# FIDO2AUTH_00212.net
KiCad netlist of a schematic drawn in EAGLE
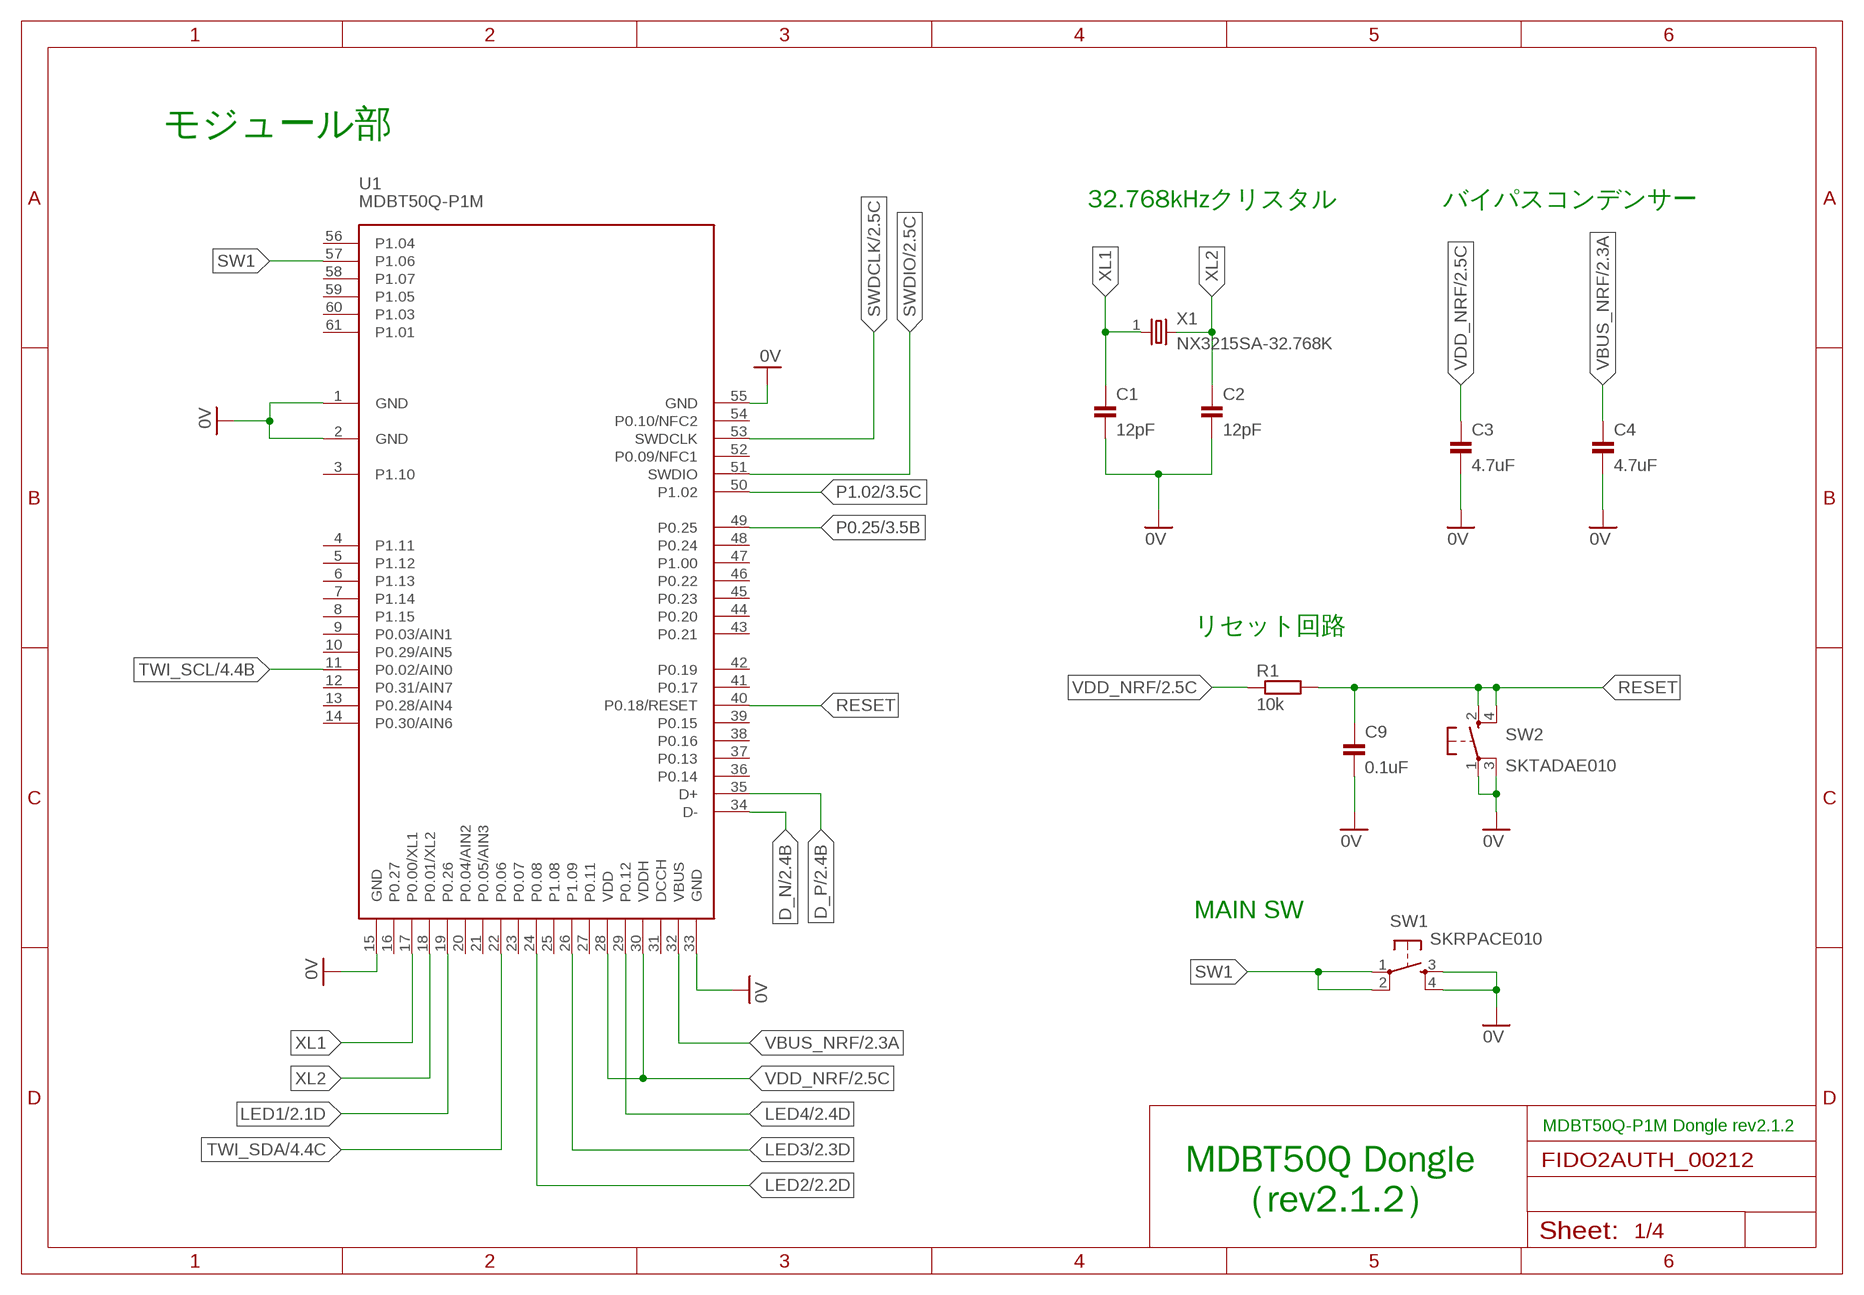
[diagram p0: schematic, sheet 1]
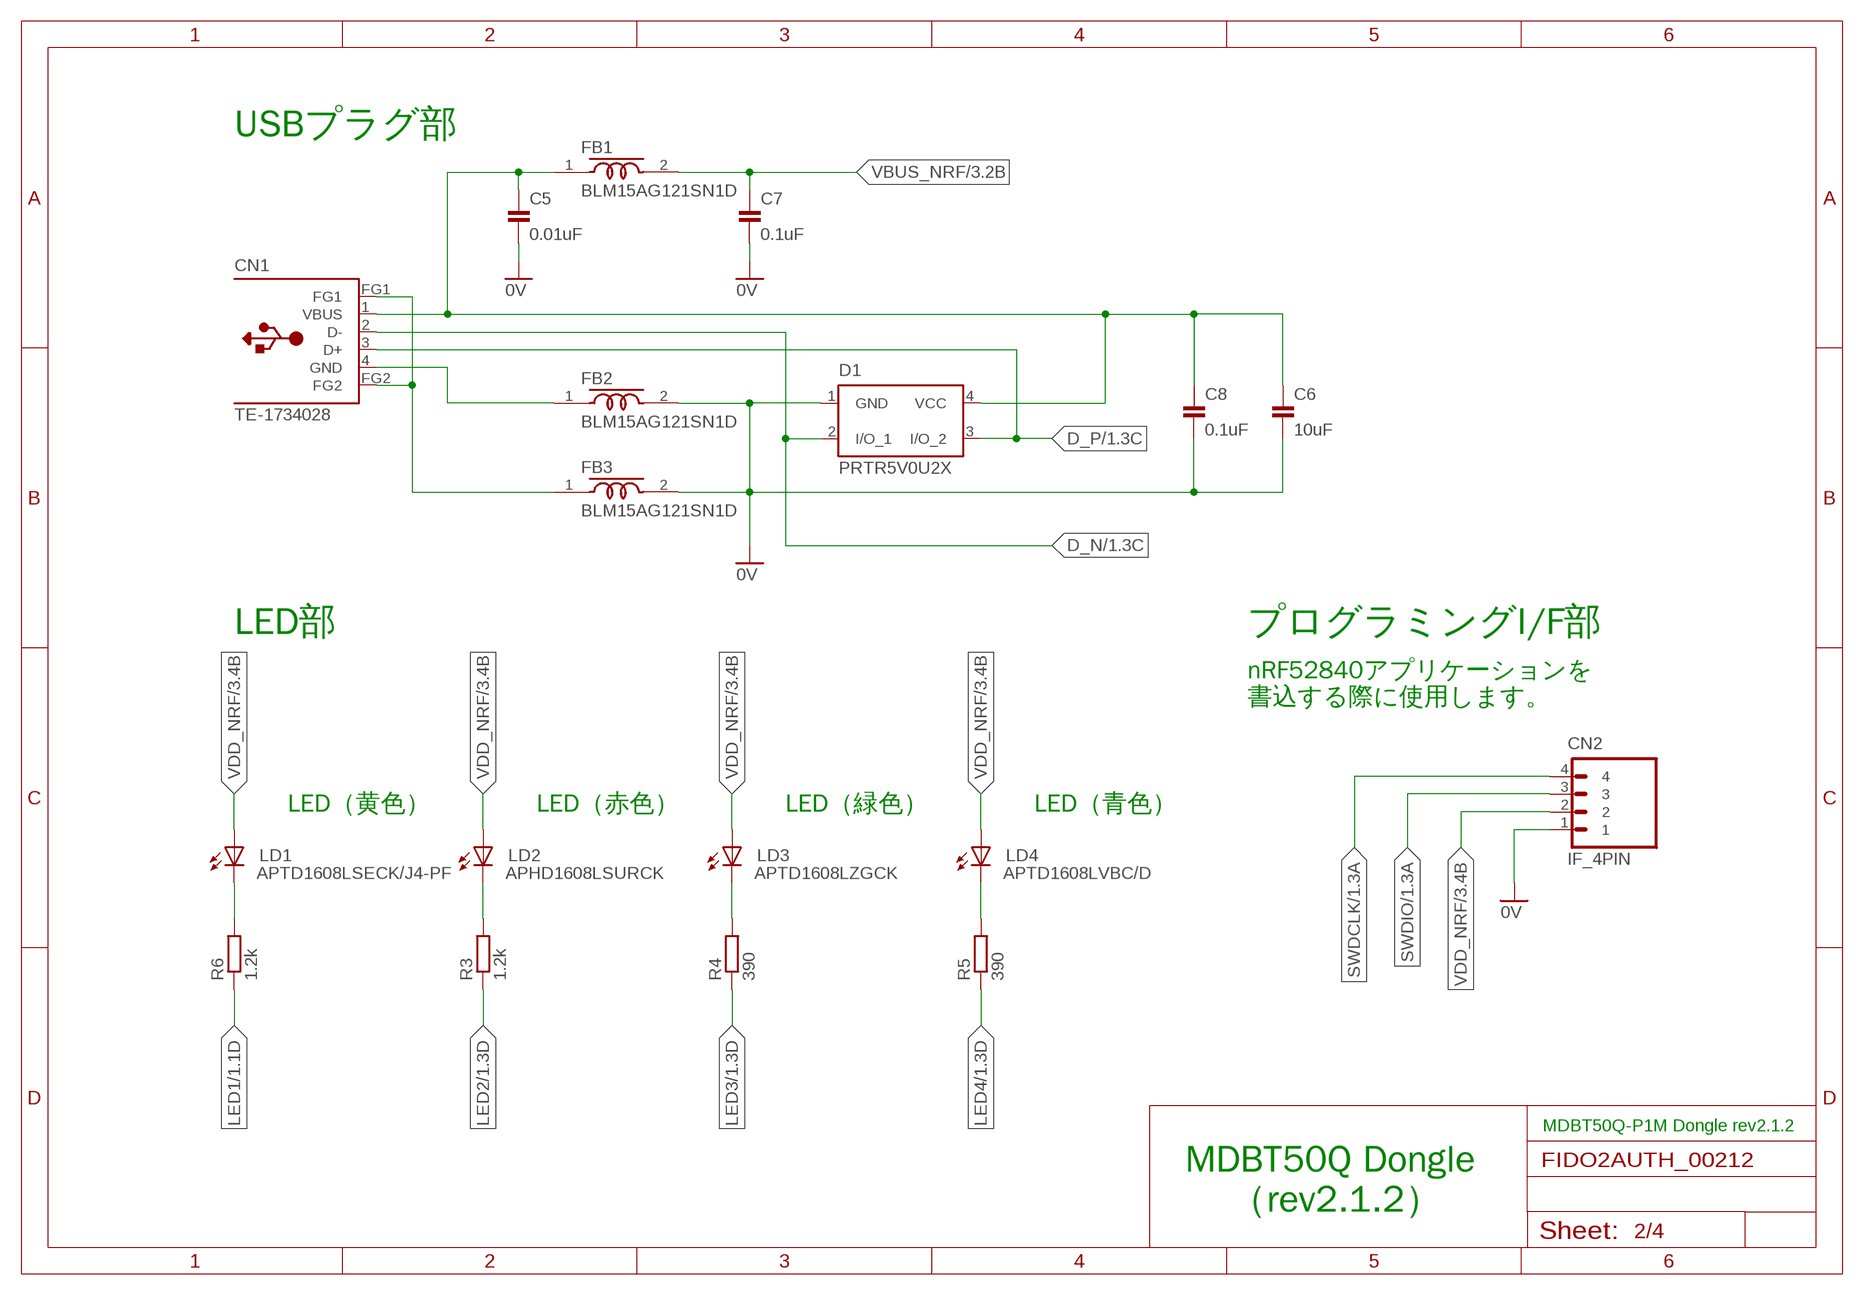
[diagram p1: schematic, sheet 2]
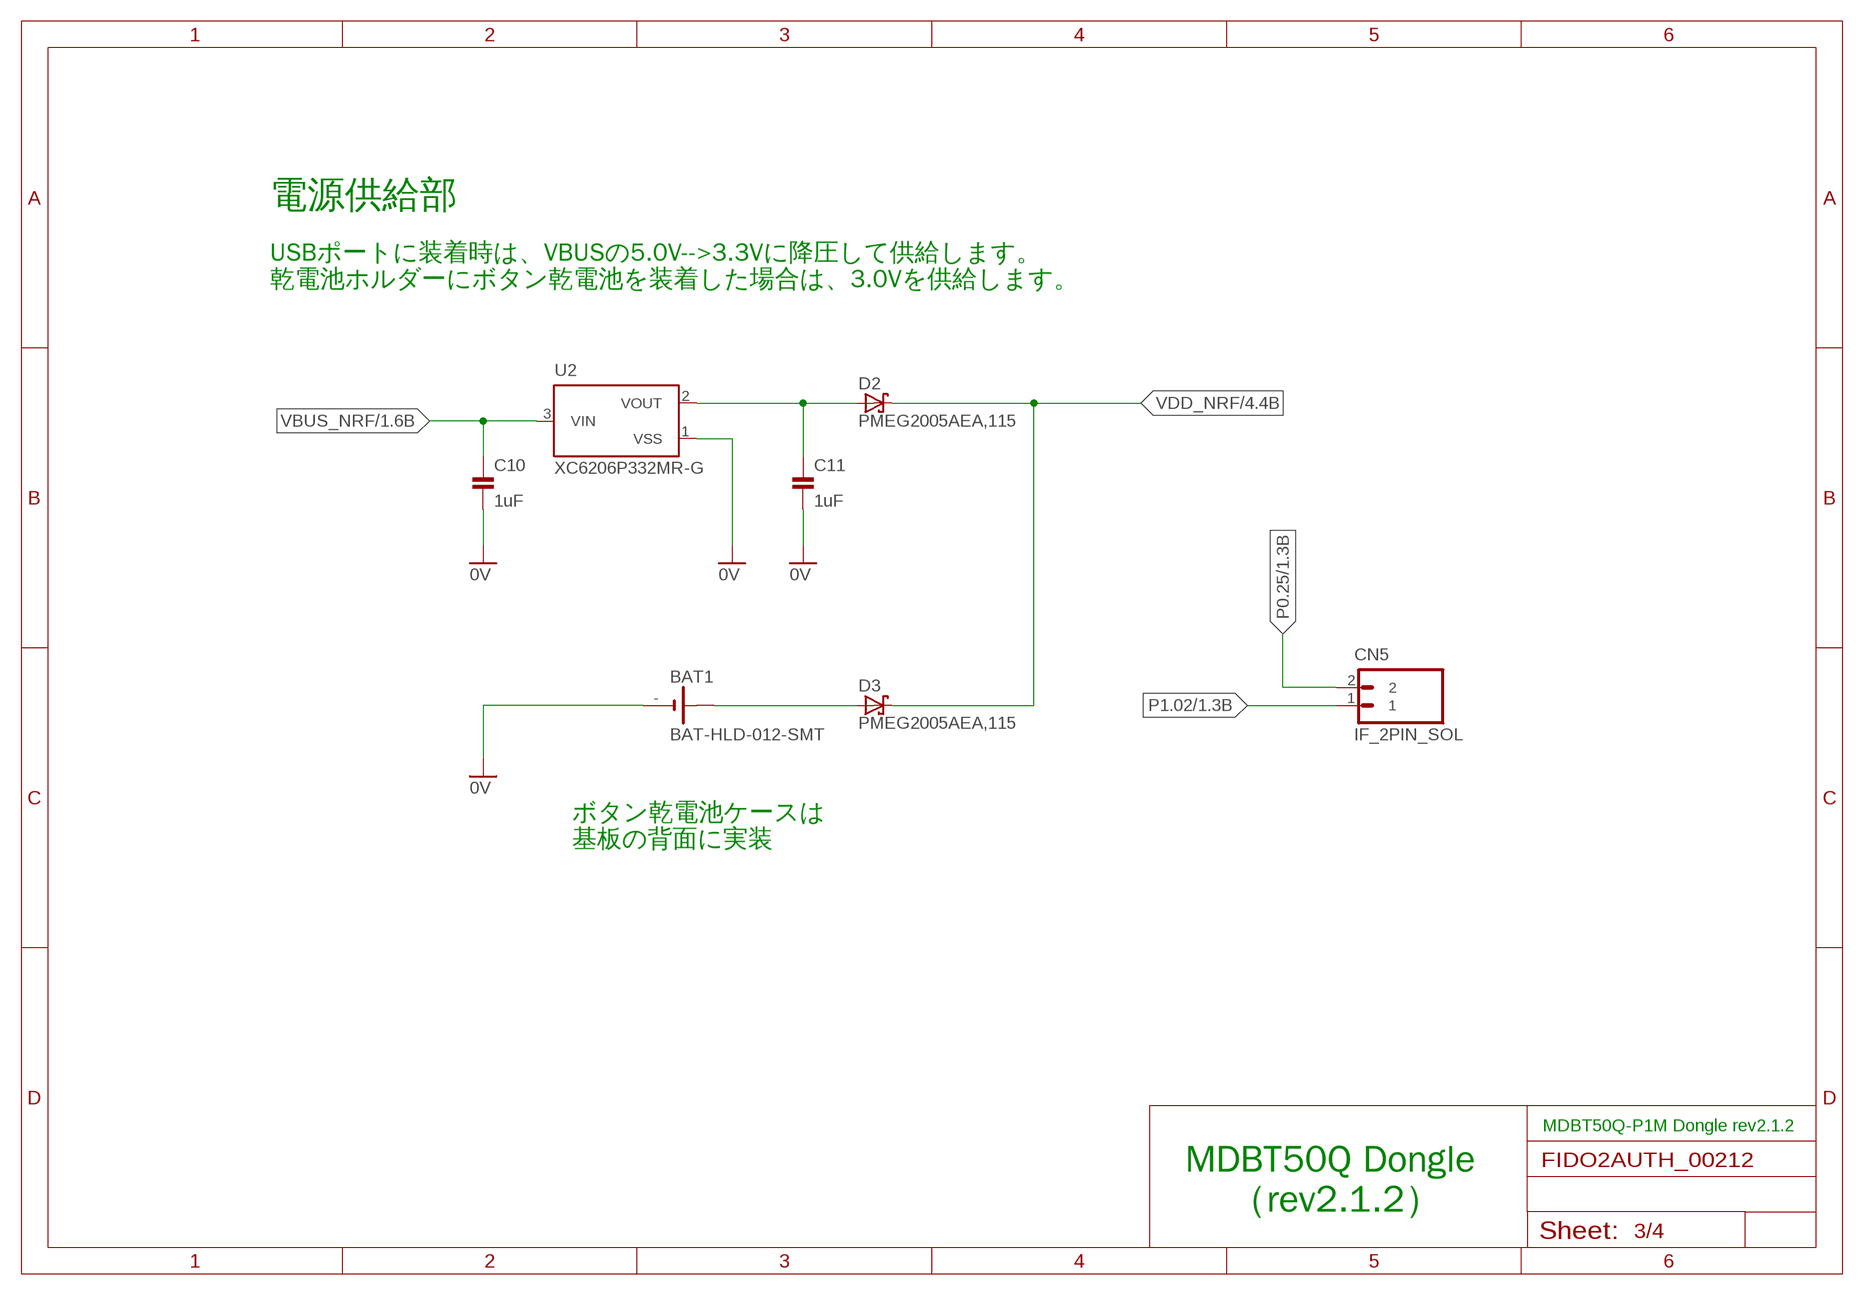
[diagram p2: schematic, sheet 3]
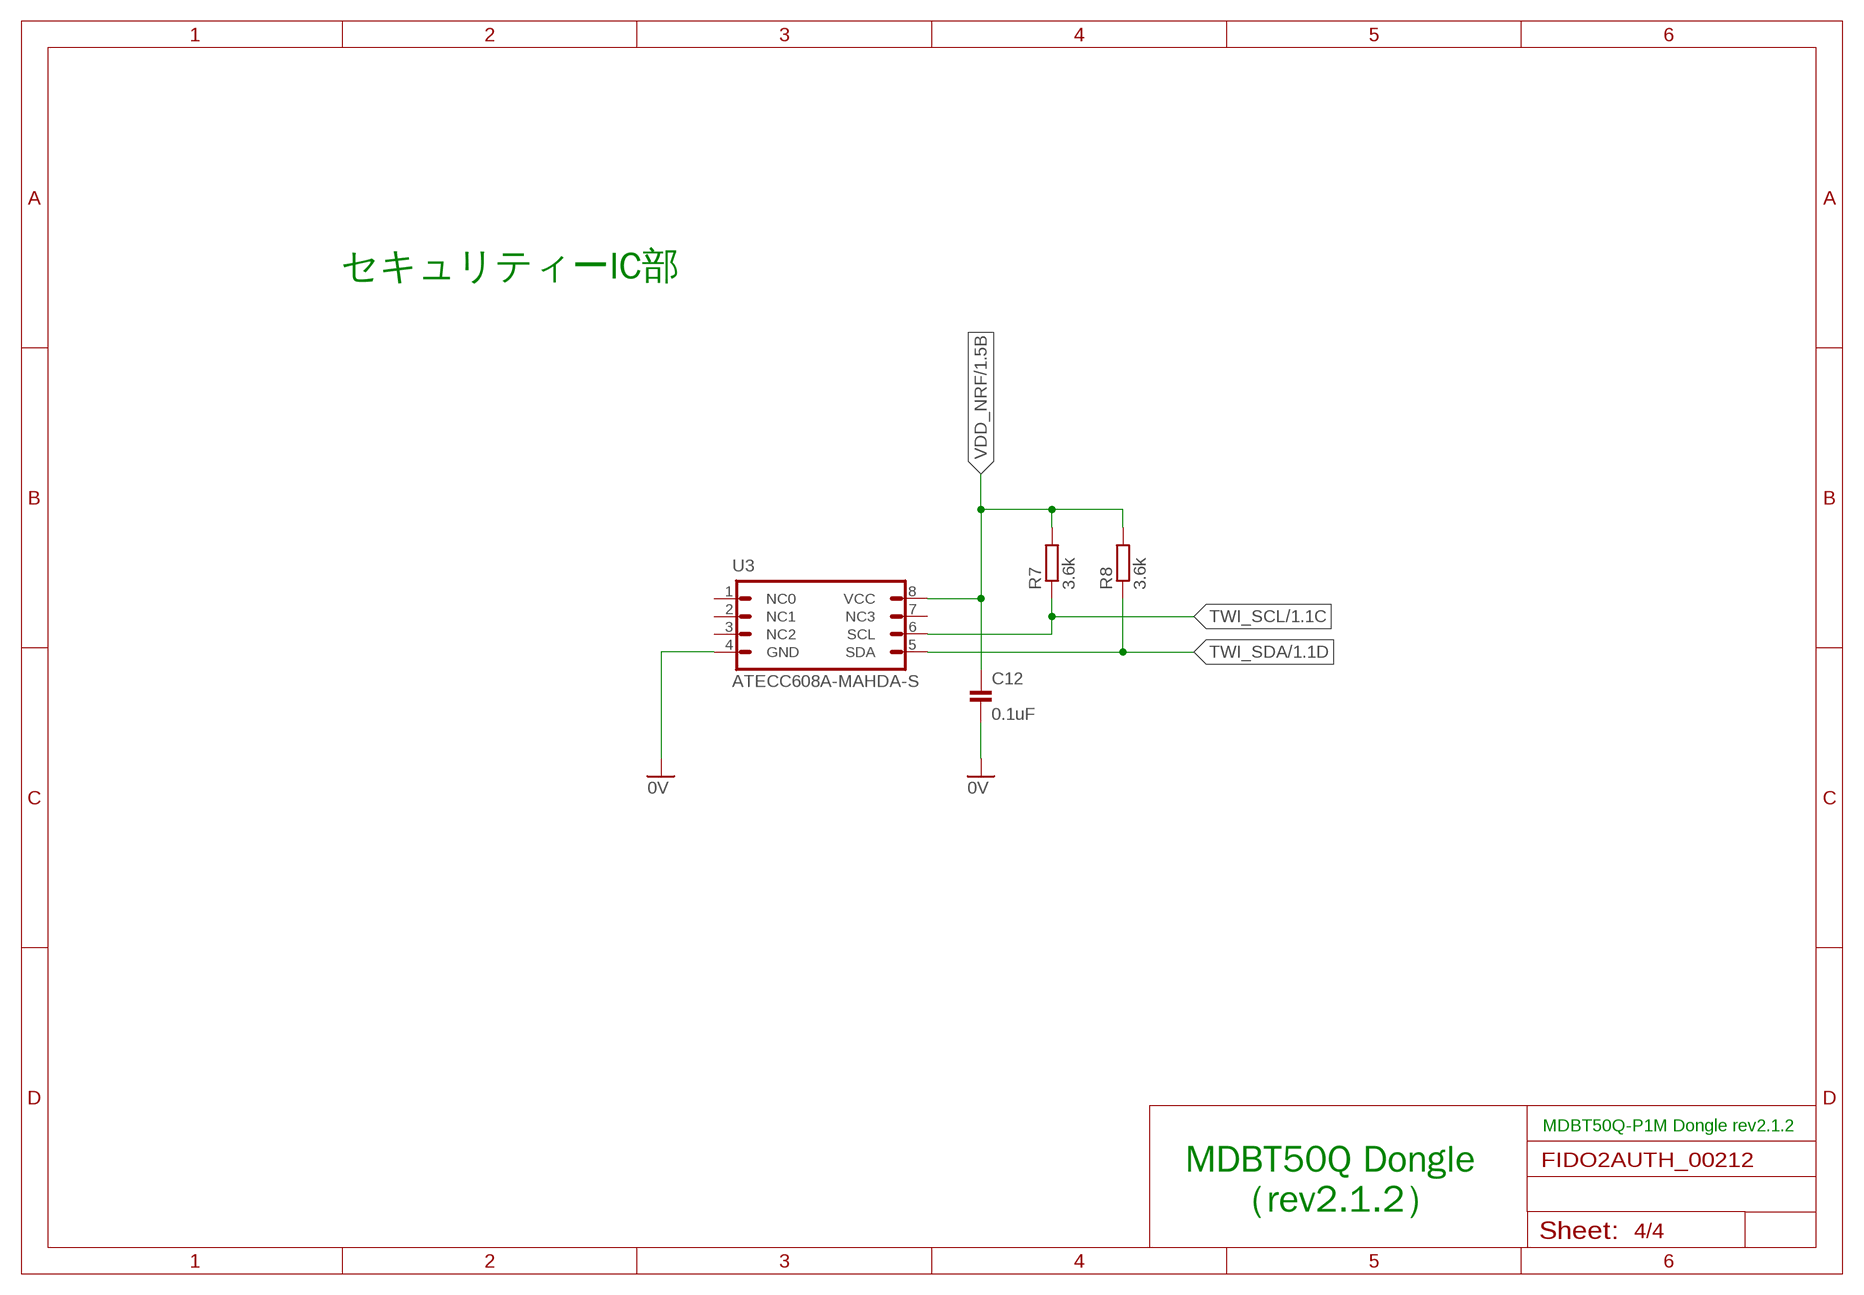
[diagram p3: schematic, sheet 4]

(export (version "E")
  (design (tool "Eeschema 10.0.6"))
  (components
    (comp (ref "C5")
      (value "0.01uF")
      (footprint "eagle-import:C0402K")
      (libsource (lib "eagle-import") (part "CAP_0402K"))
    )
    (comp (ref "C6")
      (value "10uF")
      (footprint "eagle-import:C0603K")
      (libsource (lib "eagle-import") (part "CAP_0603"))
    )
    (comp (ref "C7")
      (value "0.1uF")
      (footprint "eagle-import:C0402K")
      (libsource (lib "eagle-import") (part "CAP_0402K"))
    )
    (comp (ref "C8")
      (value "0.1uF")
      (footprint "eagle-import:C0402K")
      (libsource (lib "eagle-import") (part "CAP_0402K"))
    )
    (comp (ref "CN1")
      (value "TE-1734028")
      (footprint "eagle-import:TE-1734028")
      (libsource (lib "eagle-import") (part "TE-1734028"))
    )
    (comp (ref "CN2")
      (value "IF_4PIN")
      (footprint "eagle-import:HEADER_4PIN")
      (libsource (lib "eagle-import") (part "IF_4PIN"))
    )
    (comp (ref "D1")
      (value "PRTR5V0U2X")
      (footprint "eagle-import:SOT143B")
      (libsource (lib "eagle-import") (part "PRTR5V0U2X"))
    )
    (comp (ref "FB1")
      (value "BLM15AG121SN1D")
      (footprint "eagle-import:C0402K")
      (libsource (lib "eagle-import") (part "BLM15AG121SN1D"))
    )
    (comp (ref "FB2")
      (value "BLM15AG121SN1D")
      (footprint "eagle-import:C0402K")
      (libsource (lib "eagle-import") (part "BLM15AG121SN1D"))
    )
    (comp (ref "FB3")
      (value "BLM15AG121SN1D")
      (footprint "eagle-import:C0402K")
      (libsource (lib "eagle-import") (part "BLM15AG121SN1D"))
    )
    (comp (ref "LD1")
      (value "APTD1608LSECK/J4-PF")
      (footprint "eagle-import:APTD1608")
      (libsource (lib "eagle-import") (part "APTD1608LSECK/J4-PF"))
    )
    (comp (ref "LD2")
      (value "APHD1608LSURCK")
      (footprint "eagle-import:APTD1608")
      (libsource (lib "eagle-import") (part "APHD1608LSURCK"))
    )
    (comp (ref "LD3")
      (value "APTD1608LZGCK")
      (footprint "eagle-import:APTD1608")
      (libsource (lib "eagle-import") (part "APTD1608LZGCK"))
    )
    (comp (ref "LD4")
      (value "APTD1608LVBC/D")
      (footprint "eagle-import:APTD1608")
      (libsource (lib "eagle-import") (part "APTD1608LVBC/D"))
    )
    (comp (ref "R3")
      (value "1.2k")
      (footprint "eagle-import:R0402")
      (libsource (lib "eagle-import") (part "RESISTOR_0402"))
    )
    (comp (ref "R4")
      (value "390")
      (footprint "eagle-import:R0402")
      (libsource (lib "eagle-import") (part "RESISTOR_0402"))
    )
    (comp (ref "R5")
      (value "390")
      (footprint "eagle-import:R0402")
      (libsource (lib "eagle-import") (part "RESISTOR_0402"))
    )
    (comp (ref "R6")
      (value "1.2k")
      (footprint "eagle-import:R0402")
      (libsource (lib "eagle-import") (part "RESISTOR_0402"))
    )
    (comp (ref "C12")
      (value "0.1uF")
      (footprint "eagle-import:C0402K")
      (libsource (lib "eagle-import") (part "CAP_0402K"))
    )
    (comp (ref "R7")
      (value "3.6k")
      (footprint "eagle-import:R0402")
      (libsource (lib "eagle-import") (part "RESISTOR_0402"))
    )
    (comp (ref "R8")
      (value "3.6k")
      (footprint "eagle-import:R0402")
      (libsource (lib "eagle-import") (part "RESISTOR_0402"))
    )
    (comp (ref "U3")
      (value "ATECC608A-MAHDA-S")
      (footprint "eagle-import:DFN-2X3")
      (libsource (lib "eagle-import") (part "ATECC608A-MAHDA-S"))
    )
    (comp (ref "C1")
      (value "12pF")
      (footprint "eagle-import:C0603K")
      (libsource (lib "eagle-import") (part "CAP_0603"))
    )
    (comp (ref "C2")
      (value "12pF")
      (footprint "eagle-import:C0603K")
      (libsource (lib "eagle-import") (part "CAP_0603"))
    )
    (comp (ref "C3")
      (value "4.7uF")
      (footprint "eagle-import:C0603K")
      (libsource (lib "eagle-import") (part "CAP_0603"))
    )
    (comp (ref "C4")
      (value "4.7uF")
      (footprint "eagle-import:C0603K")
      (libsource (lib "eagle-import") (part "CAP_0603"))
    )
    (comp (ref "C9")
      (value "0.1uF")
      (footprint "eagle-import:C0402K")
      (libsource (lib "eagle-import") (part "CAP_0402K"))
    )
    (comp (ref "R1")
      (value "10k")
      (footprint "eagle-import:R0402")
      (libsource (lib "eagle-import") (part "RESISTOR_0402"))
    )
    (comp (ref "SW1")
      (value "SKRPACE010")
      (footprint "eagle-import:SKRPACE010")
      (libsource (lib "eagle-import") (part "SKRPACE010"))
    )
    (comp (ref "SW2")
      (value "SKTADAE010")
      (footprint "eagle-import:SKTADAE010")
      (libsource (lib "eagle-import") (part "SKTADAE010"))
    )
    (comp (ref "U1")
      (value "MDBT50Q-P1M")
      (footprint "eagle-import:MDBT50Q-P1M")
      (libsource (lib "eagle-import") (part "MDBT50Q-P1M"))
    )
    (comp (ref "X1")
      (value "NX3215SA-32.768K")
      (footprint "eagle-import:NX3215")
      (libsource (lib "eagle-import") (part "NX3215SA-32.768K"))
    )
    (comp (ref "BAT1")
      (value "BAT-HLD-012-SMT")
      (footprint "eagle-import:BAT-HLD-012-SMT")
      (libsource (lib "eagle-import") (part "BAT-HLD-012-SMT"))
    )
    (comp (ref "C10")
      (value "1uF")
      (footprint "eagle-import:C0603K")
      (libsource (lib "eagle-import") (part "CAP_0603"))
    )
    (comp (ref "C11")
      (value "1uF")
      (footprint "eagle-import:C0603K")
      (libsource (lib "eagle-import") (part "CAP_0603"))
    )
    (comp (ref "CN5")
      (value "IF_2PIN_SOL")
      (footprint "eagle-import:SOLPAD_2PIN")
      (libsource (lib "eagle-import") (part "IF_2PIN_SOL"))
    )
    (comp (ref "D2")
      (value "PMEG2005AEA,115")
      (footprint "eagle-import:SOD323-W")
      (libsource (lib "eagle-import") (part "PMEG2005AEA,115"))
    )
    (comp (ref "D3")
      (value "PMEG2005AEA,115")
      (footprint "eagle-import:SOD323-W")
      (libsource (lib "eagle-import") (part "PMEG2005AEA,115"))
    )
    (comp (ref "U2")
      (value "XC6206P332MR-G")
      (footprint "eagle-import:SOT23")
      (libsource (lib "eagle-import") (part "XC6206P332MR-G"))
    )
  )
  (nets
    (net (code "1") (name "0V") (class "Default")
      (node (ref "BAT1") (pin "-") (pinfunction "-_-") (pintype "passive"))
      (node (ref "C1") (pin "2") (pinfunction "2_2") (pintype "passive"))
      (node (ref "C10") (pin "2") (pinfunction "2_2") (pintype "passive"))
      (node (ref "C11") (pin "2") (pinfunction "2_2") (pintype "passive"))
      (node (ref "C12") (pin "2") (pinfunction "2_2") (pintype "passive"))
      (node (ref "C2") (pin "2") (pinfunction "2_2") (pintype "passive"))
      (node (ref "C3") (pin "2") (pinfunction "2_2") (pintype "passive"))
      (node (ref "C4") (pin "2") (pinfunction "2_2") (pintype "passive"))
      (node (ref "C5") (pin "2") (pinfunction "2_2") (pintype "passive"))
      (node (ref "C6") (pin "2") (pinfunction "2_2") (pintype "passive"))
      (node (ref "C7") (pin "2") (pinfunction "2_2") (pintype "passive"))
      (node (ref "C8") (pin "2") (pinfunction "2_2") (pintype "passive"))
      (node (ref "C9") (pin "2") (pinfunction "2_2") (pintype "passive"))
      (node (ref "CN2") (pin "1") (pinfunction "1_1") (pintype "passive"))
      (node (ref "D1") (pin "1") (pinfunction "GND_1") (pintype "passive"))
      (node (ref "FB2") (pin "2") (pinfunction "2_2") (pintype "passive"))
      (node (ref "FB3") (pin "2") (pinfunction "2_2") (pintype "passive"))
      (node (ref "SW1") (pin "3") (pinfunction "S_3") (pintype "passive"))
      (node (ref "SW1") (pin "4") (pinfunction "S1_4") (pintype "passive"))
      (node (ref "SW2") (pin "1") (pinfunction "P_1") (pintype "passive"))
      (node (ref "SW2") (pin "3") (pinfunction "P1_3") (pintype "passive"))
      (node (ref "U1") (pin "1") (pinfunction "GND_1") (pintype "bidirectional"))
      (node (ref "U1") (pin "15") (pinfunction "GND_15") (pintype "bidirectional"))
      (node (ref "U1") (pin "2") (pinfunction "GND_2") (pintype "bidirectional"))
      (node (ref "U1") (pin "33") (pinfunction "GND_33") (pintype "bidirectional"))
      (node (ref "U1") (pin "55") (pinfunction "GND_55") (pintype "bidirectional"))
      (node (ref "U2") (pin "1") (pinfunction "VSS_1") (pintype "passive"))
      (node (ref "U3") (pin "4") (pinfunction "GND_4") (pintype "passive"))
    )
    (net (code "2") (name "D_N") (class "Default")
      (node (ref "CN1") (pin "2") (pinfunction "D-_2") (pintype "bidirectional"))
      (node (ref "D1") (pin "2") (pinfunction "I/O_1_2") (pintype "bidirectional"))
      (node (ref "U1") (pin "34") (pinfunction "D-_34") (pintype "bidirectional"))
    )
    (net (code "3") (name "D_P") (class "Default")
      (node (ref "CN1") (pin "3") (pinfunction "D+_3") (pintype "bidirectional"))
      (node (ref "D1") (pin "3") (pinfunction "I/O_2_3") (pintype "bidirectional"))
      (node (ref "U1") (pin "35") (pinfunction "D+_35") (pintype "bidirectional"))
    )
    (net (code "4") (name "LED1") (class "Default")
      (node (ref "R6") (pin "1") (pinfunction "1_1") (pintype "passive"))
      (node (ref "U1") (pin "19") (pinfunction "P0.26_19") (pintype "bidirectional"))
    )
    (net (code "5") (name "LED2") (class "Default")
      (node (ref "R3") (pin "1") (pinfunction "1_1") (pintype "passive"))
      (node (ref "U1") (pin "24") (pinfunction "P0.08_24") (pintype "bidirectional"))
    )
    (net (code "6") (name "LED3") (class "Default")
      (node (ref "R4") (pin "1") (pinfunction "1_1") (pintype "passive"))
      (node (ref "U1") (pin "26") (pinfunction "P1.09_26") (pintype "bidirectional"))
    )
    (net (code "7") (name "LED4") (class "Default")
      (node (ref "R5") (pin "1") (pinfunction "1_1") (pintype "passive"))
      (node (ref "U1") (pin "29") (pinfunction "P0.12_29") (pintype "bidirectional"))
    )
    (net (code "8") (name "Net-(BAT1-+)") (class "Default")
      (node (ref "BAT1") (pin "+@1") (pinfunction "+_+@1") (pintype "passive"))
      (node (ref "D3") (pin "A") (pinfunction "A_A") (pintype "passive"))
    )
    (net (code "9") (name "Net-(CN1-GND)") (class "Default")
      (node (ref "CN1") (pin "4") (pinfunction "GND_4") (pintype "passive"))
      (node (ref "FB2") (pin "1") (pinfunction "1_1") (pintype "passive"))
    )
    (net (code "10") (name "Net-(CN1-PadFG1)") (class "Default")
      (node (ref "CN1") (pin "FG1") (pinfunction "FG1_FG1") (pintype "passive"))
      (node (ref "CN1") (pin "FG2") (pinfunction "FG2_FG2") (pintype "passive"))
      (node (ref "FB3") (pin "1") (pinfunction "1_1") (pintype "passive"))
    )
    (net (code "11") (name "Net-(CN1-VBUS)") (class "Default")
      (node (ref "C5") (pin "1") (pinfunction "1_1") (pintype "passive"))
      (node (ref "C6") (pin "1") (pinfunction "1_1") (pintype "passive"))
      (node (ref "C8") (pin "1") (pinfunction "1_1") (pintype "passive"))
      (node (ref "CN1") (pin "1") (pinfunction "VBUS_1") (pintype "passive"))
      (node (ref "D1") (pin "4") (pinfunction "VCC_4") (pintype "passive"))
      (node (ref "FB1") (pin "1") (pinfunction "1_1") (pintype "passive"))
    )
    (net (code "12") (name "Net-(LD1-PadC)") (class "Default")
      (node (ref "LD1") (pin "C") (pinfunction "C_C") (pintype "passive"))
      (node (ref "R6") (pin "2") (pinfunction "2_2") (pintype "passive"))
    )
    (net (code "13") (name "Net-(LD2-PadC)") (class "Default")
      (node (ref "LD2") (pin "C") (pinfunction "C_C") (pintype "passive"))
      (node (ref "R3") (pin "2") (pinfunction "2_2") (pintype "passive"))
    )
    (net (code "14") (name "Net-(LD3-PadC)") (class "Default")
      (node (ref "LD3") (pin "C") (pinfunction "C_C") (pintype "passive"))
      (node (ref "R4") (pin "2") (pinfunction "2_2") (pintype "passive"))
    )
    (net (code "15") (name "Net-(LD4-PadC)") (class "Default")
      (node (ref "LD4") (pin "C") (pinfunction "C_C") (pintype "passive"))
      (node (ref "R5") (pin "2") (pinfunction "2_2") (pintype "passive"))
    )
    (net (code "16") (name "Net-(U2-VOUT)") (class "Default")
      (node (ref "C11") (pin "1") (pinfunction "1_1") (pintype "passive"))
      (node (ref "D2") (pin "A") (pinfunction "A_A") (pintype "passive"))
      (node (ref "U2") (pin "2") (pinfunction "VOUT_2") (pintype "passive"))
    )
    (net (code "17") (name "P0.25") (class "Default")
      (node (ref "CN5") (pin "2") (pinfunction "2_2") (pintype "passive"))
      (node (ref "U1") (pin "49") (pinfunction "P0.25_49") (pintype "bidirectional"))
    )
    (net (code "18") (name "P1.02") (class "Default")
      (node (ref "CN5") (pin "1") (pinfunction "1_1") (pintype "passive"))
      (node (ref "U1") (pin "50") (pinfunction "P1.02_50") (pintype "bidirectional"))
    )
    (net (code "19") (name "RESET") (class "Default")
      (node (ref "C9") (pin "1") (pinfunction "1_1") (pintype "passive"))
      (node (ref "R1") (pin "2") (pinfunction "2_2") (pintype "passive"))
      (node (ref "SW2") (pin "2") (pinfunction "S_2") (pintype "passive"))
      (node (ref "SW2") (pin "4") (pinfunction "S1_4") (pintype "passive"))
      (node (ref "U1") (pin "40") (pinfunction "P0.18/RESET_40") (pintype "bidirectional"))
    )
    (net (code "20") (name "SW1") (class "Default")
      (node (ref "SW1") (pin "1") (pinfunction "P_1") (pintype "passive"))
      (node (ref "SW1") (pin "2") (pinfunction "P1_2") (pintype "passive"))
      (node (ref "U1") (pin "57") (pinfunction "P1.06_57") (pintype "bidirectional"))
    )
    (net (code "21") (name "SWDCLK") (class "Default")
      (node (ref "CN2") (pin "4") (pinfunction "4_4") (pintype "passive"))
      (node (ref "U1") (pin "53") (pinfunction "SWDCLK_53") (pintype "bidirectional"))
    )
    (net (code "22") (name "SWDIO") (class "Default")
      (node (ref "CN2") (pin "3") (pinfunction "3_3") (pintype "passive"))
      (node (ref "U1") (pin "51") (pinfunction "SWDIO_51") (pintype "bidirectional"))
    )
    (net (code "23") (name "TWI_SCL") (class "Default")
      (node (ref "R7") (pin "1") (pinfunction "1_1") (pintype "passive"))
      (node (ref "U1") (pin "11") (pinfunction "P0.02/AIN0_11") (pintype "bidirectional"))
      (node (ref "U3") (pin "6") (pinfunction "SCL_6") (pintype "bidirectional"))
    )
    (net (code "24") (name "TWI_SDA") (class "Default")
      (node (ref "R8") (pin "1") (pinfunction "1_1") (pintype "passive"))
      (node (ref "U1") (pin "22") (pinfunction "P0.06_22") (pintype "bidirectional"))
      (node (ref "U3") (pin "5") (pinfunction "SDA_5") (pintype "bidirectional"))
    )
    (net (code "25") (name "VBUS_NRF") (class "Default")
      (node (ref "C10") (pin "1") (pinfunction "1_1") (pintype "passive"))
      (node (ref "C4") (pin "1") (pinfunction "1_1") (pintype "passive"))
      (node (ref "C7") (pin "1") (pinfunction "1_1") (pintype "passive"))
      (node (ref "FB1") (pin "2") (pinfunction "2_2") (pintype "passive"))
      (node (ref "U1") (pin "32") (pinfunction "VBUS_32") (pintype "bidirectional"))
      (node (ref "U2") (pin "3") (pinfunction "VIN_3") (pintype "passive"))
    )
    (net (code "26") (name "VDD_NRF") (class "Default")
      (node (ref "C12") (pin "1") (pinfunction "1_1") (pintype "passive"))
      (node (ref "C3") (pin "1") (pinfunction "1_1") (pintype "passive"))
      (node (ref "CN2") (pin "2") (pinfunction "2_2") (pintype "passive"))
      (node (ref "D2") (pin "C") (pinfunction "C_C") (pintype "passive"))
      (node (ref "D3") (pin "C") (pinfunction "C_C") (pintype "passive"))
      (node (ref "LD1") (pin "A") (pinfunction "A_A") (pintype "passive"))
      (node (ref "LD2") (pin "A") (pinfunction "A_A") (pintype "passive"))
      (node (ref "LD3") (pin "A") (pinfunction "A_A") (pintype "passive"))
      (node (ref "LD4") (pin "A") (pinfunction "A_A") (pintype "passive"))
      (node (ref "R1") (pin "1") (pinfunction "1_1") (pintype "passive"))
      (node (ref "R7") (pin "2") (pinfunction "2_2") (pintype "passive"))
      (node (ref "R8") (pin "2") (pinfunction "2_2") (pintype "passive"))
      (node (ref "U1") (pin "28") (pinfunction "VDD_28") (pintype "bidirectional"))
      (node (ref "U1") (pin "30") (pinfunction "VDDH_30") (pintype "bidirectional"))
      (node (ref "U3") (pin "8") (pinfunction "VCC_8") (pintype "passive"))
    )
    (net (code "27") (name "XL1") (class "Default")
      (node (ref "C1") (pin "1") (pinfunction "1_1") (pintype "passive"))
      (node (ref "U1") (pin "17") (pinfunction "P0.00/XL1_17") (pintype "bidirectional"))
      (node (ref "X1") (pin "1") (pinfunction "1_1") (pintype "passive"))
    )
    (net (code "28") (name "XL2") (class "Default")
      (node (ref "C2") (pin "1") (pinfunction "1_1") (pintype "passive"))
      (node (ref "U1") (pin "18") (pinfunction "P0.01/XL2_18") (pintype "bidirectional"))
      (node (ref "X1") (pin "2") (pinfunction "2_2") (pintype "passive"))
    )
    (net (code "29") (name "unconnected-(U1-DCCH-Pad31)") (class "Default")
      (node (ref "U1") (pin "31") (pinfunction "DCCH_31") (pintype "bidirectional"))
    )
    (net (code "30") (name "unconnected-(U1-P0.03{slash}AIN1-Pad9)") (class "Default")
      (node (ref "U1") (pin "9") (pinfunction "P0.03/AIN1_9") (pintype "bidirectional"))
    )
    (net (code "31") (name "unconnected-(U1-P0.04{slash}AIN2-Pad20)") (class "Default")
      (node (ref "U1") (pin "20") (pinfunction "P0.04/AIN2_20") (pintype "bidirectional"))
    )
    (net (code "32") (name "unconnected-(U1-P0.05{slash}AIN3-Pad21)") (class "Default")
      (node (ref "U1") (pin "21") (pinfunction "P0.05/AIN3_21") (pintype "bidirectional"))
    )
    (net (code "33") (name "unconnected-(U1-P0.07-Pad23)") (class "Default")
      (node (ref "U1") (pin "23") (pinfunction "P0.07_23") (pintype "bidirectional"))
    )
    (net (code "34") (name "unconnected-(U1-P0.09{slash}NFC1-Pad52)") (class "Default")
      (node (ref "U1") (pin "52") (pinfunction "P0.09/NFC1_52") (pintype "bidirectional"))
    )
    (net (code "35") (name "unconnected-(U1-P0.10{slash}NFC2-Pad54)") (class "Default")
      (node (ref "U1") (pin "54") (pinfunction "P0.10/NFC2_54") (pintype "bidirectional"))
    )
    (net (code "36") (name "unconnected-(U1-P0.11-Pad27)") (class "Default")
      (node (ref "U1") (pin "27") (pinfunction "P0.11_27") (pintype "bidirectional"))
    )
    (net (code "37") (name "unconnected-(U1-P0.13-Pad37)") (class "Default")
      (node (ref "U1") (pin "37") (pinfunction "P0.13_37") (pintype "bidirectional"))
    )
    (net (code "38") (name "unconnected-(U1-P0.14-Pad36)") (class "Default")
      (node (ref "U1") (pin "36") (pinfunction "P0.14_36") (pintype "bidirectional"))
    )
    (net (code "39") (name "unconnected-(U1-P0.15-Pad39)") (class "Default")
      (node (ref "U1") (pin "39") (pinfunction "P0.15_39") (pintype "bidirectional"))
    )
    (net (code "40") (name "unconnected-(U1-P0.16-Pad38)") (class "Default")
      (node (ref "U1") (pin "38") (pinfunction "P0.16_38") (pintype "bidirectional"))
    )
    (net (code "41") (name "unconnected-(U1-P0.17-Pad41)") (class "Default")
      (node (ref "U1") (pin "41") (pinfunction "P0.17_41") (pintype "bidirectional"))
    )
    (net (code "42") (name "unconnected-(U1-P0.19-Pad42)") (class "Default")
      (node (ref "U1") (pin "42") (pinfunction "P0.19_42") (pintype "bidirectional"))
    )
    (net (code "43") (name "unconnected-(U1-P0.20-Pad44)") (class "Default")
      (node (ref "U1") (pin "44") (pinfunction "P0.20_44") (pintype "bidirectional"))
    )
    (net (code "44") (name "unconnected-(U1-P0.21-Pad43)") (class "Default")
      (node (ref "U1") (pin "43") (pinfunction "P0.21_43") (pintype "bidirectional"))
    )
    (net (code "45") (name "unconnected-(U1-P0.22-Pad46)") (class "Default")
      (node (ref "U1") (pin "46") (pinfunction "P0.22_46") (pintype "bidirectional"))
    )
    (net (code "46") (name "unconnected-(U1-P0.23-Pad45)") (class "Default")
      (node (ref "U1") (pin "45") (pinfunction "P0.23_45") (pintype "bidirectional"))
    )
    (net (code "47") (name "unconnected-(U1-P0.24-Pad48)") (class "Default")
      (node (ref "U1") (pin "48") (pinfunction "P0.24_48") (pintype "bidirectional"))
    )
    (net (code "48") (name "unconnected-(U1-P0.27-Pad16)") (class "Default")
      (node (ref "U1") (pin "16") (pinfunction "P0.27_16") (pintype "bidirectional"))
    )
    (net (code "49") (name "unconnected-(U1-P0.28{slash}AIN4-Pad13)") (class "Default")
      (node (ref "U1") (pin "13") (pinfunction "P0.28/AIN4_13") (pintype "bidirectional"))
    )
    (net (code "50") (name "unconnected-(U1-P0.29{slash}AIN5-Pad10)") (class "Default")
      (node (ref "U1") (pin "10") (pinfunction "P0.29/AIN5_10") (pintype "bidirectional"))
    )
    (net (code "51") (name "unconnected-(U1-P0.30{slash}AIN6-Pad14)") (class "Default")
      (node (ref "U1") (pin "14") (pinfunction "P0.30/AIN6_14") (pintype "bidirectional"))
    )
    (net (code "52") (name "unconnected-(U1-P0.31{slash}AIN7-Pad12)") (class "Default")
      (node (ref "U1") (pin "12") (pinfunction "P0.31/AIN7_12") (pintype "bidirectional"))
    )
    (net (code "53") (name "unconnected-(U1-P1.00-Pad47)") (class "Default")
      (node (ref "U1") (pin "47") (pinfunction "P1.00_47") (pintype "bidirectional"))
    )
    (net (code "54") (name "unconnected-(U1-P1.01-Pad61)") (class "Default")
      (node (ref "U1") (pin "61") (pinfunction "P1.01_61") (pintype "bidirectional"))
    )
    (net (code "55") (name "unconnected-(U1-P1.03-Pad60)") (class "Default")
      (node (ref "U1") (pin "60") (pinfunction "P1.03_60") (pintype "bidirectional"))
    )
    (net (code "56") (name "unconnected-(U1-P1.04-Pad56)") (class "Default")
      (node (ref "U1") (pin "56") (pinfunction "P1.04_56") (pintype "bidirectional"))
    )
    (net (code "57") (name "unconnected-(U1-P1.05-Pad59)") (class "Default")
      (node (ref "U1") (pin "59") (pinfunction "P1.05_59") (pintype "bidirectional"))
    )
    (net (code "58") (name "unconnected-(U1-P1.07-Pad58)") (class "Default")
      (node (ref "U1") (pin "58") (pinfunction "P1.07_58") (pintype "bidirectional"))
    )
    (net (code "59") (name "unconnected-(U1-P1.08-Pad25)") (class "Default")
      (node (ref "U1") (pin "25") (pinfunction "P1.08_25") (pintype "bidirectional"))
    )
    (net (code "60") (name "unconnected-(U1-P1.10-Pad3)") (class "Default")
      (node (ref "U1") (pin "3") (pinfunction "P1.10_3") (pintype "bidirectional"))
    )
    (net (code "61") (name "unconnected-(U1-P1.11-Pad4)") (class "Default")
      (node (ref "U1") (pin "4") (pinfunction "P1.11_4") (pintype "bidirectional"))
    )
    (net (code "62") (name "unconnected-(U1-P1.12-Pad5)") (class "Default")
      (node (ref "U1") (pin "5") (pinfunction "P1.12_5") (pintype "bidirectional"))
    )
    (net (code "63") (name "unconnected-(U1-P1.13-Pad6)") (class "Default")
      (node (ref "U1") (pin "6") (pinfunction "P1.13_6") (pintype "bidirectional"))
    )
    (net (code "64") (name "unconnected-(U1-P1.14-Pad7)") (class "Default")
      (node (ref "U1") (pin "7") (pinfunction "P1.14_7") (pintype "bidirectional"))
    )
    (net (code "65") (name "unconnected-(U1-P1.15-Pad8)") (class "Default")
      (node (ref "U1") (pin "8") (pinfunction "P1.15_8") (pintype "bidirectional"))
    )
    (net (code "66") (name "unconnected-(U3-NC0-Pad1)") (class "Default")
      (node (ref "U3") (pin "1") (pinfunction "NC0_1") (pintype "passive"))
    )
    (net (code "67") (name "unconnected-(U3-NC1-Pad2)") (class "Default")
      (node (ref "U3") (pin "2") (pinfunction "NC1_2") (pintype "passive"))
    )
    (net (code "68") (name "unconnected-(U3-NC2-Pad3)") (class "Default")
      (node (ref "U3") (pin "3") (pinfunction "NC2_3") (pintype "passive"))
    )
    (net (code "69") (name "unconnected-(U3-NC3-Pad7)") (class "Default")
      (node (ref "U3") (pin "7") (pinfunction "NC3_7") (pintype "passive"))
    )
  )
)
